# Mouse_Send_SCH.net
KiCad netlist of a schematic drawn in Altium Designer
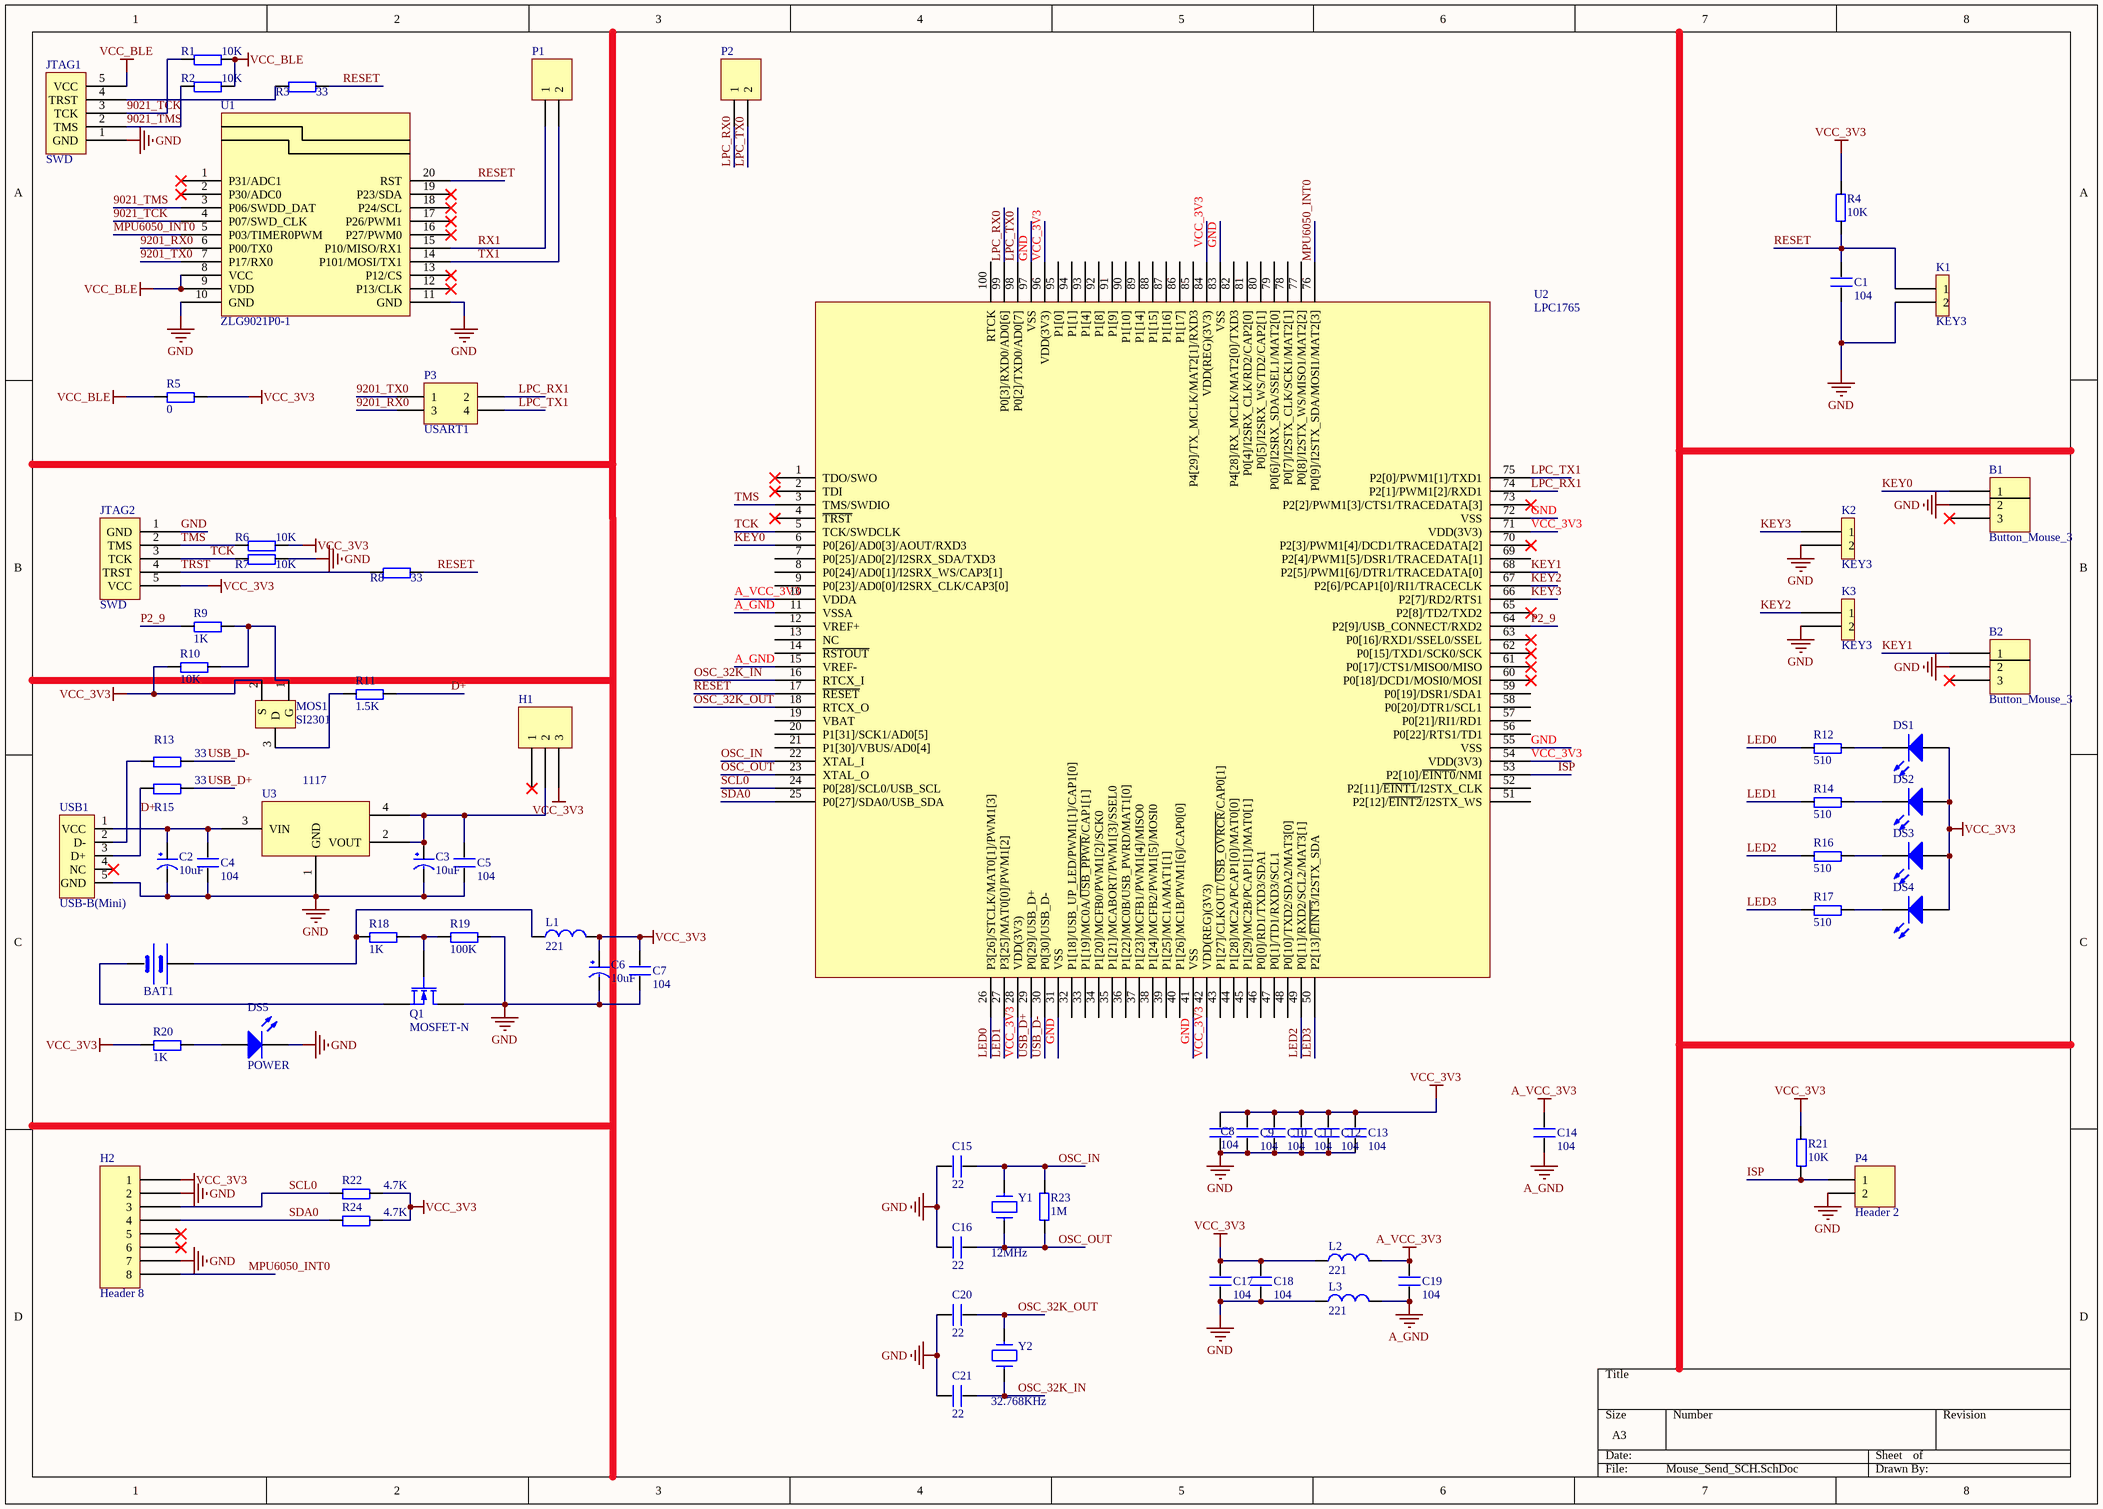
[diagram p0: Mouse_Send_SCH.SchDoc]

(export (version "E")
  (design (tool "Eeschema 10.0.6"))
  (components
    (comp (ref "B1")
      (value "Button_Mouse_3")
      (footprint "Button_Mouse_3")
      (libsource (lib "MY_SCH_Lib") (part "Button_Mouse_3"))
    )
    (comp (ref "B2")
      (value "Button_Mouse_3")
      (footprint "Button_Mouse_3")
      (libsource (lib "MY_SCH_Lib") (part "Button_Mouse_3"))
    )
    (comp (ref "BAT1") (value "BATT") (footprint "BAT_NUM5_2") (libsource (lib "MY_SCH_Lib") (part "BAT")))
    (comp (ref "C1") (value "104") (footprint "0603P") (libsource (lib "MY_SCH_Lib") (part "C")))
    (comp (ref "C2") (value "10uF") (footprint "TAJ_A") (libsource (lib "MY_SCH_Lib") (part "CAP")))
    (comp (ref "C3") (value "10uF") (footprint "TAJ_A") (libsource (lib "MY_SCH_Lib") (part "CAP")))
    (comp (ref "C4") (value "104") (footprint "0603P") (libsource (lib "MY_SCH_Lib") (part "C")))
    (comp (ref "C5") (value "104") (footprint "0603P") (libsource (lib "MY_SCH_Lib") (part "C")))
    (comp (ref "C6") (value "10uF") (footprint "TAJ_A") (libsource (lib "MY_SCH_Lib") (part "CAP")))
    (comp (ref "C7") (value "104") (footprint "0603P") (libsource (lib "MY_SCH_Lib") (part "C")))
    (comp (ref "C8") (value "104") (footprint "0603P") (libsource (lib "MY_SCH_Lib") (part "C")))
    (comp (ref "C9") (value "104") (footprint "0603P") (libsource (lib "MY_SCH_Lib") (part "C")))
    (comp (ref "C10") (value "104") (footprint "0603P") (libsource (lib "MY_SCH_Lib") (part "C")))
    (comp (ref "C11") (value "104") (footprint "0603P") (libsource (lib "MY_SCH_Lib") (part "C")))
    (comp (ref "C12") (value "104") (footprint "0603P") (libsource (lib "MY_SCH_Lib") (part "C")))
    (comp (ref "C13") (value "104") (footprint "0603P") (libsource (lib "MY_SCH_Lib") (part "C")))
    (comp (ref "C14") (value "104") (footprint "0603P") (libsource (lib "MY_SCH_Lib") (part "C")))
    (comp (ref "C15") (value "22") (footprint "0603P") (libsource (lib "MY_SCH_Lib") (part "C")))
    (comp (ref "C16") (value "22") (footprint "0603P") (libsource (lib "MY_SCH_Lib") (part "C")))
    (comp (ref "C17") (value "104") (footprint "0603P") (libsource (lib "MY_SCH_Lib") (part "C")))
    (comp (ref "C18") (value "104") (footprint "0603P") (libsource (lib "MY_SCH_Lib") (part "C")))
    (comp (ref "C19") (value "104") (footprint "0603P") (libsource (lib "MY_SCH_Lib") (part "C")))
    (comp (ref "C20") (value "22") (footprint "0603P") (libsource (lib "MY_SCH_Lib") (part "C")))
    (comp (ref "C21") (value "22") (footprint "0603P") (libsource (lib "MY_SCH_Lib") (part "C")))
    (comp (ref "DS1")
      (value "~")
      (footprint "SMDLED")
      (description "Typical RED, GREEN, YELLOW, AMBER GaAs LED")
      (fields (field (name "PUBLISHER") "Altium Limited"))
      (libsource (lib "MY_SCH_Lib") (part "LED2"))
    )
    (comp (ref "DS2")
      (value "~")
      (footprint "SMDLED")
      (description "Typical RED, GREEN, YELLOW, AMBER GaAs LED")
      (fields (field (name "PUBLISHER") "Altium Limited"))
      (libsource (lib "MY_SCH_Lib") (part "LED2"))
    )
    (comp (ref "DS3")
      (value "~")
      (footprint "SMDLED")
      (description "Typical RED, GREEN, YELLOW, AMBER GaAs LED")
      (fields (field (name "PUBLISHER") "Altium Limited"))
      (libsource (lib "MY_SCH_Lib") (part "LED2"))
    )
    (comp (ref "DS4")
      (value "~")
      (footprint "SMDLED")
      (description "Typical RED, GREEN, YELLOW, AMBER GaAs LED")
      (fields (field (name "PUBLISHER") "Altium Limited"))
      (libsource (lib "MY_SCH_Lib") (part "LED2"))
    )
    (comp (ref "DS5")
      (value "POWER")
      (footprint "SMDLED")
      (description "Typical RED, GREEN, YELLOW, AMBER GaAs LED")
      (fields (field (name "PUBLISHER") "Altium Limited"))
      (libsource (lib "MY_SCH_Lib") (part "LED2"))
    )
    (comp (ref "H1") (value "~") (footprint "KEY_B") (libsource (lib "MY_SCH_Lib") (part "Header 3")))
    (comp (ref "H2")
      (value "Header 8")
      (footprint "Header 8")
      (libsource (lib "MY_SCH_Lib") (part "Header 8"))
    )
    (comp (ref "JTAG1") (value "SWD") (footprint "HEAD5") (libsource (lib "") (part "SWD_1")))
    (comp (ref "JTAG2") (value "SWD") (footprint "HEAD5") (libsource (lib "MY_SCH_Lib") (part "SWD")))
    (comp (ref "K1") (value "KEY3") (footprint "KEY2") (libsource (lib "MY_SCH_Lib") (part "KEY3")))
    (comp (ref "K2") (value "KEY3") (footprint "KEY2") (libsource (lib "MY_SCH_Lib") (part "KEY3")))
    (comp (ref "K3") (value "KEY3") (footprint "KEY2") (libsource (lib "MY_SCH_Lib") (part "KEY3")))
    (comp (ref "L1") (value "221") (footprint "0603P") (libsource (lib "MY_SCH_Lib") (part "Inductor")))
    (comp (ref "L2") (value "221") (footprint "0603P") (libsource (lib "MY_SCH_Lib") (part "Inductor")))
    (comp (ref "L3") (value "221") (footprint "0603P") (libsource (lib "MY_SCH_Lib") (part "Inductor")))
    (comp (ref "MOS1")
      (value "SI2301")
      (footprint "SOT-23")
      (description "IRLML6401/SI2301")
      (libsource (lib "MY_SCH_Lib") (part "MOS-P"))
    )
    (comp (ref "P1")
      (value "~")
      (footprint "HDR1X2")
      (fields (field (name "PUBLISHER") "Altium Limited"))
      (libsource (lib "MY_SCH_Lib") (part "Header 2"))
    )
    (comp (ref "P2")
      (value "~")
      (footprint "HDR1X2")
      (fields (field (name "PUBLISHER") "Altium Limited"))
      (libsource (lib "MY_SCH_Lib") (part "Header 2"))
    )
    (comp (ref "P3")
      (value "USART1")
      (footprint "HDR2X2")
      (description "Header, 2-Pin, Dual row")
      (fields (field (name "PUBLISHER") "Altium Limited"))
      (libsource (lib "MY_SCH_Lib") (part "Header 2X2"))
    )
    (comp (ref "P4")
      (value "Header 2")
      (footprint "HDR1X2")
      (fields (field (name "PUBLISHER") "Altium Limited"))
      (libsource (lib "") (part "Header 2_1"))
    )
    (comp (ref "Q1")
      (value "MOSFET-N")
      (footprint "SOT-23")
      (description "N-Channel MOSFET")
      (fields (field (name "PUBLISHER") "Altium Limited"))
      (libsource (lib "Miscellaneous Devices") (part "MOSFET-N"))
    )
    (comp (ref "R1") (value "10K") (footprint "0603P") (libsource (lib "MY_SCH_Lib") (part "R")))
    (comp (ref "R2") (value "10K") (footprint "0603P") (libsource (lib "MY_SCH_Lib") (part "R")))
    (comp (ref "R3") (value "33") (footprint "0603P") (libsource (lib "MY_SCH_Lib") (part "R")))
    (comp (ref "R4") (value "10K") (footprint "0603P") (libsource (lib "MY_SCH_Lib") (part "R")))
    (comp (ref "R5") (value "0") (footprint "0603P") (libsource (lib "MY_SCH_Lib") (part "R")))
    (comp (ref "R6") (value "10K") (footprint "0603P") (libsource (lib "MY_SCH_Lib") (part "R")))
    (comp (ref "R7") (value "10K") (footprint "0603P") (libsource (lib "MY_SCH_Lib") (part "R")))
    (comp (ref "R8") (value "33") (footprint "0603P") (libsource (lib "MY_SCH_Lib") (part "R")))
    (comp (ref "R9") (value "1K") (footprint "0603P") (libsource (lib "MY_SCH_Lib") (part "R")))
    (comp (ref "R10") (value "10K") (footprint "0603P") (libsource (lib "MY_SCH_Lib") (part "R")))
    (comp (ref "R11") (value "1.5K") (footprint "0603P") (libsource (lib "MY_SCH_Lib") (part "R")))
    (comp (ref "R12") (value "510") (footprint "0603P") (libsource (lib "MY_SCH_Lib") (part "R")))
    (comp (ref "R13") (value "33") (footprint "0603P") (libsource (lib "MY_SCH_Lib") (part "R")))
    (comp (ref "R14") (value "510") (footprint "0603P") (libsource (lib "MY_SCH_Lib") (part "R")))
    (comp (ref "R15") (value "33") (footprint "0603P") (libsource (lib "MY_SCH_Lib") (part "R")))
    (comp (ref "R16") (value "510") (footprint "0603P") (libsource (lib "MY_SCH_Lib") (part "R")))
    (comp (ref "R17") (value "510") (footprint "0603P") (libsource (lib "MY_SCH_Lib") (part "R")))
    (comp (ref "R18") (value "1K") (footprint "0603P") (libsource (lib "MY_SCH_Lib") (part "R")))
    (comp (ref "R19") (value "100K") (footprint "0603P") (libsource (lib "MY_SCH_Lib") (part "R")))
    (comp (ref "R20") (value "1K") (footprint "0603P") (libsource (lib "MY_SCH_Lib") (part "R")))
    (comp (ref "R21") (value "10K") (footprint "0603P") (libsource (lib "MY_SCH_Lib") (part "R")))
    (comp (ref "R22") (value "4.7K") (footprint "0603P") (libsource (lib "MY_SCH_Lib") (part "R")))
    (comp (ref "R23") (value "1M") (footprint "0603P") (libsource (lib "MY_SCH_Lib") (part "R")))
    (comp (ref "R24") (value "4.7K") (footprint "0603P") (libsource (lib "MY_SCH_Lib") (part "R")))
    (comp (ref "U1")
      (value "ZLG9021P0-1")
      (footprint "ZLG9021P0-1")
      (libsource (lib "MY_SCH_Lib") (part "ZLG9021P0-1"))
    )
    (comp (ref "U2")
      (value "LPC1765")
      (footprint "TQFP-100")
      (libsource (lib "LPC17xx_System_Sch_AD") (part "LPC1765"))
    )
    (comp (ref "U3") (value "1117") (footprint "AMS1117") (libsource (lib "MY_SCH_Lib") (part "1117")))
    (comp (ref "USB1")
      (value "USB-B(Mini)")
      (footprint "USB/SM0.8-6H5")
      (libsource (lib "MY_SCH_Lib") (part "USB5"))
    )
    (comp (ref "Y1")
      (value "12MHz")
      (footprint "XTAL_US")
      (description "Crystal")
      (libsource (lib "LPC17xx_System_Sch_AD") (part "CRYSTAL"))
    )
    (comp (ref "Y2")
      (value "32.768KHz")
      (footprint "CRY-32")
      (description "Crystal")
      (libsource (lib "LPC17xx_System_Sch_AD") (part "CRYSTAL"))
    )
  )
  (nets
    (net (code "1") (name "/9021_TCK") (class "Default")
      (node (ref "JTAG1") (pin "3") (pinfunction "TCK_3") (pintype "passive"))
      (node (ref "R1") (pin "1") (pintype "passive"))
      (node (ref "U1") (pin "4") (pinfunction "P07/SWD_CLK_4") (pintype "passive"))
    )
    (net (code "2") (name "/9021_TMS") (class "Default")
      (node (ref "JTAG1") (pin "2") (pinfunction "TMS_2") (pintype "passive"))
      (node (ref "R2") (pin "1") (pintype "passive"))
      (node (ref "U1") (pin "3") (pinfunction "P06/SWDD_DAT_3") (pintype "passive"))
    )
    (net (code "3") (name "/9201_RX0") (class "Default")
      (node (ref "P3") (pin "3") (pinfunction "3_3") (pintype "passive"))
      (node (ref "U1") (pin "6") (pinfunction "P00/TX0_6") (pintype "passive"))
    )
    (net (code "4") (name "/9201_TX0") (class "Default")
      (node (ref "P3") (pin "1") (pinfunction "1_1") (pintype "passive"))
      (node (ref "U1") (pin "7") (pinfunction "P17/RX0_7") (pintype "passive"))
    )
    (net (code "5") (name "/D+") (class "Default")
      (node (ref "R11") (pin "2") (pintype "passive"))
      (node (ref "R15") (pin "1") (pintype "passive"))
      (node (ref "USB1") (pin "3") (pinfunction "D+_3") (pintype "passive"))
    )
    (net (code "6") (name "/ISP") (class "Default")
      (node (ref "P4") (pin "1") (pinfunction "1_1") (pintype "passive"))
      (node (ref "R21") (pin "1") (pintype "passive"))
      (node (ref "U2") (pin "53") (pinfunction "P2[10]/~{EINT0}/NMI_53") (pintype "passive"))
    )
    (net (code "7") (name "/KEY0") (class "Default")
      (node (ref "B1") (pin "1") (pinfunction "1_1") (pintype "passive"))
      (node (ref "U2") (pin "6") (pinfunction "P0[26]/AD0[3]/AOUT/RXD3_6") (pintype "passive"))
    )
    (net (code "8") (name "/KEY1") (class "Default")
      (node (ref "B2") (pin "1") (pinfunction "1_1") (pintype "passive"))
      (node (ref "U2") (pin "68") (pinfunction "P2[5]/PWM1[6]/DTR1/TRACEDATA[0]_68") (pintype "passive"))
    )
    (net (code "9") (name "/KEY2") (class "Default")
      (node (ref "K3") (pin "1") (pinfunction "1_1") (pintype "passive"))
      (node (ref "U2") (pin "67") (pinfunction "P2[6]/PCAP1[0]/RI1/TRACECLK_67") (pintype "passive"))
    )
    (net (code "10") (name "/KEY3") (class "Default")
      (node (ref "K2") (pin "1") (pinfunction "1_1") (pintype "passive"))
      (node (ref "U2") (pin "66") (pinfunction "P2[7]/RD2/RTS1_66") (pintype "passive"))
    )
    (net (code "11") (name "/LED0") (class "Default")
      (node (ref "R12") (pin "1") (pintype "passive"))
      (node (ref "U2") (pin "26") (pinfunction "P3[26]/STCLK/MAT0[1]/PWM1[3]_26") (pintype "passive"))
    )
    (net (code "12") (name "/LED1") (class "Default")
      (node (ref "R14") (pin "1") (pintype "passive"))
      (node (ref "U2") (pin "27") (pinfunction "P3[25]/MAT0[0]/PWM1[2]_27") (pintype "passive"))
    )
    (net (code "13") (name "/LED2") (class "Default")
      (node (ref "R16") (pin "1") (pintype "passive"))
      (node (ref "U2") (pin "49") (pinfunction "P0[11]/RXD2/SCL2/MAT3[1]_49") (pintype "passive"))
    )
    (net (code "14") (name "/LED3") (class "Default")
      (node (ref "R17") (pin "1") (pintype "passive"))
      (node (ref "U2") (pin "50") (pinfunction "P2[13]/~{EINT3}/I2STX_SDA_50") (pintype "passive"))
    )
    (net (code "15") (name "/LPC_RX0") (class "Default")
      (node (ref "P2") (pin "1") (pinfunction "1_1") (pintype "passive"))
      (node (ref "U2") (pin "99") (pinfunction "P0[3]/RXD0/AD0[6]_99") (pintype "passive"))
    )
    (net (code "16") (name "/LPC_RX1") (class "Default")
      (node (ref "P3") (pin "2") (pinfunction "2_2") (pintype "passive"))
      (node (ref "U2") (pin "74") (pinfunction "P2[1]/PWM1[2]/RXD1_74") (pintype "passive"))
    )
    (net (code "17") (name "/LPC_TX0") (class "Default")
      (node (ref "P2") (pin "2") (pinfunction "2_2") (pintype "passive"))
      (node (ref "U2") (pin "98") (pinfunction "P0[2]/TXD0/AD0[7]_98") (pintype "passive"))
    )
    (net (code "18") (name "/LPC_TX1") (class "Default")
      (node (ref "P3") (pin "4") (pinfunction "4_4") (pintype "passive"))
      (node (ref "U2") (pin "75") (pinfunction "P2[0]/PWM1[1]/TXD1_75") (pintype "passive"))
    )
    (net (code "19") (name "/MPU6050_INT0") (class "Default")
      (node (ref "H2") (pin "8") (pinfunction "8_8") (pintype "passive"))
      (node (ref "U1") (pin "5") (pinfunction "P03/TIMER0PWM_5") (pintype "passive"))
      (node (ref "U2") (pin "76") (pinfunction "P0[9]/I2STX_SDA/MOSI1/MAT2[3]_76") (pintype "passive"))
    )
    (net (code "20") (name "/OSC_32K_IN") (class "Default")
      (node (ref "C21") (pin "2") (pintype "passive"))
      (node (ref "U2") (pin "16") (pinfunction "RTCX_I_16") (pintype "passive"))
      (node (ref "Y2") (pin "1") (pinfunction "1_1") (pintype "passive"))
    )
    (net (code "21") (name "/OSC_32K_OUT") (class "Default")
      (node (ref "C20") (pin "2") (pintype "passive"))
      (node (ref "U2") (pin "18") (pinfunction "RTCX_O_18") (pintype "passive"))
      (node (ref "Y2") (pin "2") (pinfunction "2_2") (pintype "passive"))
    )
    (net (code "22") (name "/OSC_IN") (class "Default")
      (node (ref "C15") (pin "2") (pintype "passive"))
      (node (ref "R23") (pin "1") (pintype "passive"))
      (node (ref "U2") (pin "22") (pinfunction "XTAL_I_22") (pintype "passive"))
      (node (ref "Y1") (pin "2") (pinfunction "2_2") (pintype "passive"))
    )
    (net (code "23") (name "/OSC_OUT") (class "Default")
      (node (ref "C16") (pin "2") (pintype "passive"))
      (node (ref "R23") (pin "2") (pintype "passive"))
      (node (ref "U2") (pin "23") (pinfunction "XTAL_O_23") (pintype "passive"))
      (node (ref "Y1") (pin "1") (pinfunction "1_1") (pintype "passive"))
    )
    (net (code "24") (name "/P2_9") (class "Default")
      (node (ref "R9") (pin "1") (pintype "passive"))
      (node (ref "U2") (pin "64") (pinfunction "P2[9]/USB_CONNECT/RXD2_64") (pintype "passive"))
    )
    (net (code "25") (name "/RESET") (class "Default")
      (node (ref "C1") (pin "2") (pintype "passive"))
      (node (ref "K1") (pin "1") (pinfunction "1_1") (pintype "passive"))
      (node (ref "R3") (pin "2") (pintype "passive"))
      (node (ref "R4") (pin "1") (pintype "passive"))
      (node (ref "R8") (pin "2") (pintype "passive"))
      (node (ref "U1") (pin "20") (pinfunction "RST_20") (pintype "passive"))
      (node (ref "U2") (pin "17") (pinfunction "~{RESET}_17") (pintype "passive"))
    )
    (net (code "26") (name "/RX1") (class "Default")
      (node (ref "P1") (pin "1") (pinfunction "1_1") (pintype "passive"))
      (node (ref "U1") (pin "15") (pinfunction "P10/MISO/RX1_15") (pintype "passive"))
    )
    (net (code "27") (name "/SCL0") (class "Default")
      (node (ref "H2") (pin "3") (pinfunction "3_3") (pintype "passive"))
      (node (ref "R22") (pin "1") (pintype "passive"))
      (node (ref "U2") (pin "24") (pinfunction "P0[28]/SCL0/USB_SCL_24") (pintype "passive"))
    )
    (net (code "28") (name "/SDA0") (class "Default")
      (node (ref "H2") (pin "4") (pinfunction "4_4") (pintype "passive"))
      (node (ref "R24") (pin "1") (pintype "passive"))
      (node (ref "U2") (pin "25") (pinfunction "P0[27]/SDA0/USB_SDA_25") (pintype "passive"))
    )
    (net (code "29") (name "/TCK") (class "Default")
      (node (ref "JTAG2") (pin "3") (pinfunction "TCK_3") (pintype "passive"))
      (node (ref "R7") (pin "1") (pintype "passive"))
      (node (ref "U2") (pin "5") (pinfunction "TCK/SWDCLK_5") (pintype "passive"))
    )
    (net (code "30") (name "/TMS") (class "Default")
      (node (ref "JTAG2") (pin "2") (pinfunction "TMS_2") (pintype "passive"))
      (node (ref "R6") (pin "1") (pintype "passive"))
      (node (ref "U2") (pin "3") (pinfunction "TMS/SWDIO_3") (pintype "passive"))
    )
    (net (code "31") (name "/TRST") (class "Default")
      (node (ref "JTAG2") (pin "4") (pinfunction "TRST_4") (pintype "passive"))
      (node (ref "R8") (pin "1") (pintype "passive"))
    )
    (net (code "32") (name "/TX1") (class "Default")
      (node (ref "P1") (pin "2") (pinfunction "2_2") (pintype "passive"))
      (node (ref "U1") (pin "14") (pinfunction "P101/MOSI/TX1_14") (pintype "passive"))
    )
    (net (code "33") (name "/USB_D+") (class "Default")
      (node (ref "R15") (pin "2") (pintype "passive"))
      (node (ref "U2") (pin "29") (pinfunction "P0[29]/USB_D+_29") (pintype "passive"))
    )
    (net (code "34") (name "/USB_D-") (class "Default")
      (node (ref "R13") (pin "2") (pintype "passive"))
      (node (ref "U2") (pin "30") (pinfunction "P0[30]/USB_D-_30") (pintype "passive"))
    )
    (net (code "35") (name "A_GND") (class "Default")
      (node (ref "C14") (pin "2") (pintype "passive"))
      (node (ref "C19") (pin "1") (pintype "passive"))
      (node (ref "L3") (pin "2") (pinfunction "2_2") (pintype "passive"))
      (node (ref "U2") (pin "11") (pinfunction "VSSA_11") (pintype "passive"))
      (node (ref "U2") (pin "15") (pinfunction "VREF-_15") (pintype "passive"))
    )
    (net (code "36") (name "A_VCC_3V3") (class "Default")
      (node (ref "C14") (pin "1") (pintype "passive"))
      (node (ref "C19") (pin "2") (pintype "passive"))
      (node (ref "L2") (pin "2") (pinfunction "2_2") (pintype "passive"))
      (node (ref "U2") (pin "10") (pinfunction "VDDA_10") (pintype "passive"))
    )
    (net (code "37") (name "GND") (class "Default")
      (node (ref "B1") (pin "2") (pinfunction "2_2") (pintype "passive"))
      (node (ref "B2") (pin "2") (pinfunction "2_2") (pintype "passive"))
      (node (ref "C1") (pin "1") (pintype "passive"))
      (node (ref "C10") (pin "2") (pintype "passive"))
      (node (ref "C11") (pin "2") (pintype "passive"))
      (node (ref "C12") (pin "2") (pintype "passive"))
      (node (ref "C13") (pin "2") (pintype "passive"))
      (node (ref "C15") (pin "1") (pintype "passive"))
      (node (ref "C16") (pin "1") (pintype "passive"))
      (node (ref "C17") (pin "1") (pintype "passive"))
      (node (ref "C18") (pin "1") (pintype "passive"))
      (node (ref "C2") (pin "2") (pinfunction "GND_2") (pintype "passive"))
      (node (ref "C20") (pin "1") (pintype "passive"))
      (node (ref "C21") (pin "1") (pintype "passive"))
      (node (ref "C3") (pin "2") (pinfunction "GND_2") (pintype "passive"))
      (node (ref "C4") (pin "1") (pintype "passive"))
      (node (ref "C5") (pin "1") (pintype "passive"))
      (node (ref "C6") (pin "2") (pinfunction "GND_2") (pintype "passive"))
      (node (ref "C7") (pin "1") (pintype "passive"))
      (node (ref "C8") (pin "2") (pintype "passive"))
      (node (ref "C9") (pin "2") (pintype "passive"))
      (node (ref "DS5") (pin "2") (pinfunction "K_2") (pintype "passive"))
      (node (ref "H2") (pin "2") (pinfunction "2_2") (pintype "passive"))
      (node (ref "H2") (pin "7") (pinfunction "7_7") (pintype "passive"))
      (node (ref "JTAG1") (pin "1") (pinfunction "GND_1") (pintype "passive"))
      (node (ref "JTAG2") (pin "1") (pinfunction "GND_1") (pintype "passive"))
      (node (ref "K1") (pin "2") (pinfunction "2_2") (pintype "passive"))
      (node (ref "K2") (pin "2") (pinfunction "2_2") (pintype "passive"))
      (node (ref "K3") (pin "2") (pinfunction "2_2") (pintype "passive"))
      (node (ref "L3") (pin "1") (pinfunction "1_1") (pintype "passive"))
      (node (ref "P4") (pin "2") (pinfunction "2_2") (pintype "passive"))
      (node (ref "Q1") (pin "1") (pinfunction "D_1") (pintype "passive"))
      (node (ref "R19") (pin "2") (pintype "passive"))
      (node (ref "R7") (pin "2") (pintype "passive"))
      (node (ref "U1") (pin "10") (pinfunction "GND_10") (pintype "passive"))
      (node (ref "U1") (pin "11") (pinfunction "GND_11") (pintype "passive"))
      (node (ref "U2") (pin "31") (pinfunction "VSS_31") (pintype "passive"))
      (node (ref "U2") (pin "41") (pinfunction "VSS_41") (pintype "passive"))
      (node (ref "U2") (pin "55") (pinfunction "VSS_55") (pintype "passive"))
      (node (ref "U2") (pin "72") (pinfunction "VSS_72") (pintype "passive"))
      (node (ref "U2") (pin "83") (pinfunction "VSS_83") (pintype "passive"))
      (node (ref "U2") (pin "97") (pinfunction "VSS_97") (pintype "passive"))
      (node (ref "U3") (pin "1") (pinfunction "GND_1") (pintype "passive"))
      (node (ref "USB1") (pin "5") (pinfunction "GND_5") (pintype "passive"))
    )
    (net (code "38") (name "Net-(BAT1-GND)") (class "Default")
      (node (ref "BAT1") (pin "2") (pinfunction "GND_2") (pintype "passive"))
      (node (ref "Q1") (pin "3") (pinfunction "S_3") (pintype "passive"))
    )
    (net (code "39") (name "Net-(BAT1-VCC)") (class "Default")
      (node (ref "BAT1") (pin "1") (pinfunction "VCC_1") (pintype "passive"))
      (node (ref "L1") (pin "1") (pinfunction "1_1") (pintype "passive"))
      (node (ref "R18") (pin "1") (pintype "passive"))
    )
    (net (code "40") (name "Net-(C2-VCC)") (class "Default")
      (node (ref "C2") (pin "1") (pinfunction "VCC_1") (pintype "passive"))
      (node (ref "C4") (pin "2") (pintype "passive"))
      (node (ref "U3") (pin "3") (pinfunction "VIN_3") (pintype "passive"))
      (node (ref "USB1") (pin "1") (pinfunction "VCC_1") (pintype "passive"))
    )
    (net (code "41") (name "Net-(C3-VCC)") (class "Default")
      (node (ref "C3") (pin "1") (pinfunction "VCC_1") (pintype "passive"))
      (node (ref "C5") (pin "2") (pintype "passive"))
      (node (ref "H1") (pin "2") (pinfunction "2_2") (pintype "passive"))
      (node (ref "U3") (pin "2") (pinfunction "VOUT_2") (pintype "passive"))
      (node (ref "U3") (pin "4") (pinfunction "4_4") (pintype "passive"))
    )
    (net (code "42") (name "Net-(DS1-K)") (class "Default")
      (node (ref "DS1") (pin "2") (pinfunction "K_2") (pintype "passive"))
      (node (ref "R12") (pin "2") (pintype "passive"))
    )
    (net (code "43") (name "Net-(DS2-K)") (class "Default")
      (node (ref "DS2") (pin "2") (pinfunction "K_2") (pintype "passive"))
      (node (ref "R14") (pin "2") (pintype "passive"))
    )
    (net (code "44") (name "Net-(DS3-K)") (class "Default")
      (node (ref "DS3") (pin "2") (pinfunction "K_2") (pintype "passive"))
      (node (ref "R16") (pin "2") (pintype "passive"))
    )
    (net (code "45") (name "Net-(DS4-K)") (class "Default")
      (node (ref "DS4") (pin "2") (pinfunction "K_2") (pintype "passive"))
      (node (ref "R17") (pin "2") (pintype "passive"))
    )
    (net (code "46") (name "Net-(DS5-A)") (class "Default")
      (node (ref "DS5") (pin "1") (pinfunction "A_1") (pintype "passive"))
      (node (ref "R20") (pin "2") (pintype "passive"))
    )
    (net (code "47") (name "Net-(JTAG1-TRST)") (class "Default")
      (node (ref "JTAG1") (pin "4") (pinfunction "TRST_4") (pintype "passive"))
      (node (ref "R3") (pin "1") (pintype "passive"))
    )
    (net (code "48") (name "Net-(MOS1-D)") (class "Default")
      (node (ref "MOS1") (pin "3") (pinfunction "D_3") (pintype "passive"))
      (node (ref "R11") (pin "1") (pintype "passive"))
    )
    (net (code "49") (name "Net-(MOS1-G)") (class "Default")
      (node (ref "MOS1") (pin "1") (pinfunction "G_1") (pintype "passive"))
      (node (ref "R10") (pin "2") (pintype "passive"))
      (node (ref "R9") (pin "2") (pintype "passive"))
    )
    (net (code "50") (name "Net-(Q1-G)") (class "Default")
      (node (ref "Q1") (pin "2") (pinfunction "G_2") (pintype "passive"))
      (node (ref "R18") (pin "2") (pintype "passive"))
      (node (ref "R19") (pin "1") (pintype "passive"))
    )
    (net (code "51") (name "Net-(USB1-D-)") (class "Default")
      (node (ref "R13") (pin "1") (pintype "passive"))
      (node (ref "USB1") (pin "2") (pinfunction "D-_2") (pintype "passive"))
    )
    (net (code "52") (name "VCC_3V3") (class "Default")
      (node (ref "C10") (pin "1") (pintype "passive"))
      (node (ref "C11") (pin "1") (pintype "passive"))
      (node (ref "C12") (pin "1") (pintype "passive"))
      (node (ref "C13") (pin "1") (pintype "passive"))
      (node (ref "C17") (pin "2") (pintype "passive"))
      (node (ref "C18") (pin "2") (pintype "passive"))
      (node (ref "C6") (pin "1") (pinfunction "VCC_1") (pintype "passive"))
      (node (ref "C7") (pin "2") (pintype "passive"))
      (node (ref "C8") (pin "1") (pintype "passive"))
      (node (ref "C9") (pin "1") (pintype "passive"))
      (node (ref "DS1") (pin "1") (pinfunction "A_1") (pintype "passive"))
      (node (ref "DS2") (pin "1") (pinfunction "A_1") (pintype "passive"))
      (node (ref "DS3") (pin "1") (pinfunction "A_1") (pintype "passive"))
      (node (ref "DS4") (pin "1") (pinfunction "A_1") (pintype "passive"))
      (node (ref "H1") (pin "3") (pinfunction "3_3") (pintype "passive"))
      (node (ref "H2") (pin "1") (pinfunction "1_1") (pintype "passive"))
      (node (ref "JTAG2") (pin "5") (pinfunction "VCC_5") (pintype "passive"))
      (node (ref "L1") (pin "2") (pinfunction "2_2") (pintype "passive"))
      (node (ref "L2") (pin "1") (pinfunction "1_1") (pintype "passive"))
      (node (ref "MOS1") (pin "2") (pinfunction "S_2") (pintype "passive"))
      (node (ref "R10") (pin "1") (pintype "passive"))
      (node (ref "R20") (pin "1") (pintype "passive"))
      (node (ref "R21") (pin "2") (pintype "passive"))
      (node (ref "R22") (pin "2") (pintype "passive"))
      (node (ref "R24") (pin "2") (pintype "passive"))
      (node (ref "R4") (pin "2") (pintype "passive"))
      (node (ref "R5") (pin "2") (pintype "passive"))
      (node (ref "R6") (pin "2") (pintype "passive"))
      (node (ref "U2") (pin "28") (pinfunction "VDD(3V3)_28") (pintype "passive"))
      (node (ref "U2") (pin "42") (pinfunction "VDD(REG)(3V3)_42") (pintype "passive"))
      (node (ref "U2") (pin "54") (pinfunction "VDD(3V3)_54") (pintype "passive"))
      (node (ref "U2") (pin "71") (pinfunction "VDD(3V3)_71") (pintype "passive"))
      (node (ref "U2") (pin "84") (pinfunction "VDD(REG)(3V3)_84") (pintype "passive"))
      (node (ref "U2") (pin "96") (pinfunction "VDD(3V3)_96") (pintype "passive"))
    )
    (net (code "53") (name "VCC_BLE") (class "Default")
      (node (ref "JTAG1") (pin "5") (pinfunction "VCC_5") (pintype "passive"))
      (node (ref "R1") (pin "2") (pintype "passive"))
      (node (ref "R2") (pin "2") (pintype "passive"))
      (node (ref "R5") (pin "1") (pintype "passive"))
      (node (ref "U1") (pin "8") (pinfunction "VCC_8") (pintype "passive"))
      (node (ref "U1") (pin "9") (pinfunction "VDD_9") (pintype "passive"))
    )
    (net (code "54") (name "unconnected-(B1-Pad3)") (class "Default")
      (node (ref "B1") (pin "3") (pinfunction "3_3") (pintype "passive+no_connect"))
    )
    (net (code "55") (name "unconnected-(B2-Pad3)") (class "Default")
      (node (ref "B2") (pin "3") (pinfunction "3_3") (pintype "passive+no_connect"))
    )
    (net (code "56") (name "unconnected-(H1-Pad1)") (class "Default")
      (node (ref "H1") (pin "1") (pinfunction "1_1") (pintype "passive+no_connect"))
    )
    (net (code "57") (name "unconnected-(H2-Pad5)") (class "Default")
      (node (ref "H2") (pin "5") (pinfunction "5_5") (pintype "passive+no_connect"))
    )
    (net (code "58") (name "unconnected-(H2-Pad6)") (class "Default")
      (node (ref "H2") (pin "6") (pinfunction "6_6") (pintype "passive+no_connect"))
    )
    (net (code "59") (name "unconnected-(U1-P12{slash}CS-Pad13)") (class "Default")
      (node (ref "U1") (pin "13") (pinfunction "P12/CS_13") (pintype "passive+no_connect"))
    )
    (net (code "60") (name "unconnected-(U1-P13{slash}CLK-Pad12)") (class "Default")
      (node (ref "U1") (pin "12") (pinfunction "P13/CLK_12") (pintype "passive+no_connect"))
    )
    (net (code "61") (name "unconnected-(U1-P23{slash}SDA-Pad19)") (class "Default")
      (node (ref "U1") (pin "19") (pinfunction "P23/SDA_19") (pintype "passive+no_connect"))
    )
    (net (code "62") (name "unconnected-(U1-P24{slash}SCL-Pad18)") (class "Default")
      (node (ref "U1") (pin "18") (pinfunction "P24/SCL_18") (pintype "passive+no_connect"))
    )
    (net (code "63") (name "unconnected-(U1-P26{slash}PWM1-Pad17)") (class "Default")
      (node (ref "U1") (pin "17") (pinfunction "P26/PWM1_17") (pintype "passive+no_connect"))
    )
    (net (code "64") (name "unconnected-(U1-P27{slash}PWM0-Pad16)") (class "Default")
      (node (ref "U1") (pin "16") (pinfunction "P27/PWM0_16") (pintype "passive+no_connect"))
    )
    (net (code "65") (name "unconnected-(U1-P30{slash}ADC0-Pad2)") (class "Default")
      (node (ref "U1") (pin "2") (pinfunction "P30/ADC0_2") (pintype "passive+no_connect"))
    )
    (net (code "66") (name "unconnected-(U1-P31{slash}ADC1-Pad1)") (class "Default")
      (node (ref "U1") (pin "1") (pinfunction "P31/ADC1_1") (pintype "passive+no_connect"))
    )
    (net (code "67") (name "unconnected-(U2-NC-Pad13)") (class "Default")
      (node (ref "U2") (pin "13") (pinfunction "NC_13") (pintype "passive"))
    )
    (net (code "68") (name "unconnected-(U2-P0[0]{slash}RD1{slash}TXD3{slash}SDA1-Pad46)") (class "Default")
      (node (ref "U2") (pin "46") (pinfunction "P0[0]/RD1/TXD3/SDA1_46") (pintype "passive"))
    )
    (net (code "69") (name "unconnected-(U2-P0[1]{slash}TD1{slash}RXD3{slash}SCL1-Pad47)") (class "Default")
      (node (ref "U2") (pin "47") (pinfunction "P0[1]/TD1/RXD3/SCL1_47") (pintype "passive"))
    )
    (net (code "70") (name "unconnected-(U2-P0[4]{slash}I2SRX_CLK{slash}RD2{slash}CAP2[0]-Pad81)") (class "Default")
      (node (ref "U2") (pin "81") (pinfunction "P0[4]/I2SRX_CLK/RD2/CAP2[0]_81") (pintype "passive"))
    )
    (net (code "71") (name "unconnected-(U2-P0[5]{slash}I2SRX_WS{slash}TD2{slash}CAP2[1]-Pad80)") (class "Default")
      (node (ref "U2") (pin "80") (pinfunction "P0[5]/I2SRX_WS/TD2/CAP2[1]_80") (pintype "passive"))
    )
    (net (code "72") (name "unconnected-(U2-P0[6]{slash}I2SRX_SDA{slash}SSEL1{slash}MAT2[0]-Pad79)") (class "Default")
      (node (ref "U2") (pin "79") (pinfunction "P0[6]/I2SRX_SDA/SSEL1/MAT2[0]_79") (pintype "passive"))
    )
    (net (code "73") (name "unconnected-(U2-P0[7]{slash}I2STX_CLK{slash}SCK1{slash}MAT2[1]-Pad78)") (class "Default")
      (node (ref "U2") (pin "78") (pinfunction "P0[7]/I2STX_CLK/SCK1/MAT2[1]_78") (pintype "passive"))
    )
    (net (code "74") (name "unconnected-(U2-P0[8]{slash}I2STX_WS{slash}MISO1{slash}MAT2[2]-Pad77)") (class "Default")
      (node (ref "U2") (pin "77") (pinfunction "P0[8]/I2STX_WS/MISO1/MAT2[2]_77") (pintype "passive"))
    )
    (net (code "75") (name "unconnected-(U2-P0[10]{slash}TXD2{slash}SDA2{slash}MAT3[0]-Pad48)") (class "Default")
      (node (ref "U2") (pin "48") (pinfunction "P0[10]/TXD2/SDA2/MAT3[0]_48") (pintype "passive"))
    )
    (net (code "76") (name "unconnected-(U2-P0[15]{slash}TXD1{slash}SCK0{slash}SCK-Pad62)") (class "Default")
      (node (ref "U2") (pin "62") (pinfunction "P0[15]/TXD1/SCK0/SCK_62") (pintype "passive+no_connect"))
    )
    (net (code "77") (name "unconnected-(U2-P0[16]{slash}RXD1{slash}SSEL0{slash}SSEL-Pad63)") (class "Default")
      (node (ref "U2") (pin "63") (pinfunction "P0[16]/RXD1/SSEL0/SSEL_63") (pintype "passive+no_connect"))
    )
    (net (code "78") (name "unconnected-(U2-P0[17]{slash}CTS1{slash}MISO0{slash}MISO-Pad61)") (class "Default")
      (node (ref "U2") (pin "61") (pinfunction "P0[17]/CTS1/MISO0/MISO_61") (pintype "passive+no_connect"))
    )
    (net (code "79") (name "unconnected-(U2-P0[18]{slash}DCD1{slash}MOSI0{slash}MOSI-Pad60)") (class "Default")
      (node (ref "U2") (pin "60") (pinfunction "P0[18]/DCD1/MOSI0/MOSI_60") (pintype "passive+no_connect"))
    )
    (net (code "80") (name "unconnected-(U2-P0[19]{slash}DSR1{slash}SDA1-Pad59)") (class "Default")
      (node (ref "U2") (pin "59") (pinfunction "P0[19]/DSR1/SDA1_59") (pintype "passive"))
    )
    (net (code "81") (name "unconnected-(U2-P0[20]{slash}DTR1{slash}SCL1-Pad58)") (class "Default")
      (node (ref "U2") (pin "58") (pinfunction "P0[20]/DTR1/SCL1_58") (pintype "passive"))
    )
    (net (code "82") (name "unconnected-(U2-P0[21]{slash}RI1{slash}RD1-Pad57)") (class "Default")
      (node (ref "U2") (pin "57") (pinfunction "P0[21]/RI1/RD1_57") (pintype "passive"))
    )
    (net (code "83") (name "unconnected-(U2-P0[22]{slash}RTS1{slash}TD1-Pad56)") (class "Default")
      (node (ref "U2") (pin "56") (pinfunction "P0[22]/RTS1/TD1_56") (pintype "passive"))
    )
    (net (code "84") (name "unconnected-(U2-P0[23]{slash}AD0[0]{slash}I2SRX_CLK{slash}CAP3[0]-Pad9)") (class "Default")
      (node (ref "U2") (pin "9") (pinfunction "P0[23]/AD0[0]/I2SRX_CLK/CAP3[0]_9") (pintype "passive"))
    )
    (net (code "85") (name "unconnected-(U2-P0[24]{slash}AD0[1]{slash}I2SRX_WS{slash}CAP3[1]-Pad8)") (class "Default")
      (node (ref "U2") (pin "8") (pinfunction "P0[24]/AD0[1]/I2SRX_WS/CAP3[1]_8") (pintype "passive"))
    )
    (net (code "86") (name "unconnected-(U2-P0[25]{slash}AD0[2]{slash}I2SRX_SDA{slash}TXD3-Pad7)") (class "Default")
      (node (ref "U2") (pin "7") (pinfunction "P0[25]/AD0[2]/I2SRX_SDA/TXD3_7") (pintype "passive"))
    )
    (net (code "87") (name "unconnected-(U2-P1[0]-Pad95)") (class "Default")
      (node (ref "U2") (pin "95") (pinfunction "P1[0]_95") (pintype "passive"))
    )
    (net (code "88") (name "unconnected-(U2-P1[1]-Pad94)") (class "Default")
      (node (ref "U2") (pin "94") (pinfunction "P1[1]_94") (pintype "passive"))
    )
    (net (code "89") (name "unconnected-(U2-P1[4]-Pad93)") (class "Default")
      (node (ref "U2") (pin "93") (pinfunction "P1[4]_93") (pintype "passive"))
    )
    (net (code "90") (name "unconnected-(U2-P1[8]-Pad92)") (class "Default")
      (node (ref "U2") (pin "92") (pinfunction "P1[8]_92") (pintype "passive"))
    )
    (net (code "91") (name "unconnected-(U2-P1[9]-Pad91)") (class "Default")
      (node (ref "U2") (pin "91") (pinfunction "P1[9]_91") (pintype "passive"))
    )
    (net (code "92") (name "unconnected-(U2-P1[10]-Pad90)") (class "Default")
      (node (ref "U2") (pin "90") (pinfunction "P1[10]_90") (pintype "passive"))
    )
    (net (code "93") (name "unconnected-(U2-P1[14]-Pad89)") (class "Default")
      (node (ref "U2") (pin "89") (pinfunction "P1[14]_89") (pintype "passive"))
    )
    (net (code "94") (name "unconnected-(U2-P1[15]-Pad88)") (class "Default")
      (node (ref "U2") (pin "88") (pinfunction "P1[15]_88") (pintype "passive"))
    )
    (net (code "95") (name "unconnected-(U2-P1[16]-Pad87)") (class "Default")
      (node (ref "U2") (pin "87") (pinfunction "P1[16]_87") (pintype "passive"))
    )
    (net (code "96") (name "unconnected-(U2-P1[17]-Pad86)") (class "Default")
      (node (ref "U2") (pin "86") (pinfunction "P1[17]_86") (pintype "passive"))
    )
    (net (code "97") (name "unconnected-(U2-P1[18]{slash}USB_UP_LED{slash}PWM1[1]{slash}CAP1[0]-Pad32)") (class "Default")
      (node (ref "U2") (pin "32") (pinfunction "P1[18]/USB_UP_LED/PWM1[1]/CAP1[0]_32") (pintype "passive"))
    )
    (net (code "98") (name "unconnected-(U2-P1[19]{slash}MC0A{slash}~{USB_PPWR}{slash}CAP1[1]-Pad33)") (class "Default")
      (node (ref "U2") (pin "33") (pinfunction "P1[19]/MC0A/~{USB_PPWR}/CAP1[1]_33") (pintype "passive"))
    )
    (net (code "99") (name "unconnected-(U2-P1[20]{slash}MCFB0{slash}PWM1[2]{slash}SCK0-Pad34)") (class "Default")
      (node (ref "U2") (pin "34") (pinfunction "P1[20]/MCFB0/PWM1[2]/SCK0_34") (pintype "passive"))
    )
    (net (code "100") (name "unconnected-(U2-P1[21]{slash}MCABORT{slash}PWM1[3]{slash}SSEL0-Pad35)") (class "Default")
      (node (ref "U2") (pin "35") (pinfunction "P1[21]/MCABORT/PWM1[3]/SSEL0_35") (pintype "passive"))
    )
    (net (code "101") (name "unconnected-(U2-P1[22]{slash}MC0B{slash}USB_PWRD{slash}MAT1[0]-Pad36)") (class "Default")
      (node (ref "U2") (pin "36") (pinfunction "P1[22]/MC0B/USB_PWRD/MAT1[0]_36") (pintype "passive"))
    )
    (net (code "102") (name "unconnected-(U2-P1[23]{slash}MCFB1{slash}PWM1[4]{slash}MISO0-Pad37)") (class "Default")
      (node (ref "U2") (pin "37") (pinfunction "P1[23]/MCFB1/PWM1[4]/MISO0_37") (pintype "passive"))
    )
    (net (code "103") (name "unconnected-(U2-P1[24]{slash}MCFB2{slash}PWM1[5]{slash}MOSI0-Pad38)") (class "Default")
      (node (ref "U2") (pin "38") (pinfunction "P1[24]/MCFB2/PWM1[5]/MOSI0_38") (pintype "passive"))
    )
    (net (code "104") (name "unconnected-(U2-P1[25]{slash}MC1A{slash}MAT1[1]-Pad39)") (class "Default")
      (node (ref "U2") (pin "39") (pinfunction "P1[25]/MC1A/MAT1[1]_39") (pintype "passive"))
    )
    (net (code "105") (name "unconnected-(U2-P1[26]{slash}MC1B{slash}PWM1[6]{slash}CAP0[0]-Pad40)") (class "Default")
      (node (ref "U2") (pin "40") (pinfunction "P1[26]/MC1B/PWM1[6]/CAP0[0]_40") (pintype "passive"))
    )
    (net (code "106") (name "unconnected-(U2-P1[27]{slash}CLKOUT{slash}~{USB_OVRCR}{slash}CAP0[1]-Pad43)") (class "Default")
      (node (ref "U2") (pin "43") (pinfunction "P1[27]/CLKOUT/~{USB_OVRCR}/CAP0[1]_43") (pintype "passive"))
    )
    (net (code "107") (name "unconnected-(U2-P1[28]{slash}MC2A{slash}PCAP1[0]{slash}MAT0[0]-Pad44)") (class "Default")
      (node (ref "U2") (pin "44") (pinfunction "P1[28]/MC2A/PCAP1[0]/MAT0[0]_44") (pintype "passive"))
    )
    (net (code "108") (name "unconnected-(U2-P1[29]{slash}MC2B{slash}PCAP1[1]{slash}MAT0[1]-Pad45)") (class "Default")
      (node (ref "U2") (pin "45") (pinfunction "P1[29]/MC2B/PCAP1[1]/MAT0[1]_45") (pintype "passive"))
    )
    (net (code "109") (name "unconnected-(U2-P1[30]{slash}VBUS{slash}AD0[4]-Pad21)") (class "Default")
      (node (ref "U2") (pin "21") (pinfunction "P1[30]/VBUS/AD0[4]_21") (pintype "passive"))
    )
    (net (code "110") (name "unconnected-(U2-P1[31]{slash}SCK1{slash}AD0[5]-Pad20)") (class "Default")
      (node (ref "U2") (pin "20") (pinfunction "P1[31]/SCK1/AD0[5]_20") (pintype "passive"))
    )
    (net (code "111") (name "unconnected-(U2-P2[2]{slash}PWM1[3]{slash}CTS1{slash}TRACEDATA[3]-Pad73)") (class "Default")
      (node (ref "U2") (pin "73") (pinfunction "P2[2]/PWM1[3]/CTS1/TRACEDATA[3]_73") (pintype "passive+no_connect"))
    )
    (net (code "112") (name "unconnected-(U2-P2[3]{slash}PWM1[4]{slash}DCD1{slash}TRACEDATA[2]-Pad70)") (class "Default")
      (node (ref "U2") (pin "70") (pinfunction "P2[3]/PWM1[4]/DCD1/TRACEDATA[2]_70") (pintype "passive+no_connect"))
    )
    (net (code "113") (name "unconnected-(U2-P2[4]{slash}PWM1[5]{slash}DSR1{slash}TRACEDATA[1]-Pad69)") (class "Default")
      (node (ref "U2") (pin "69") (pinfunction "P2[4]/PWM1[5]/DSR1/TRACEDATA[1]_69") (pintype "passive"))
    )
    (net (code "114") (name "unconnected-(U2-P2[8]{slash}TD2{slash}TXD2-Pad65)") (class "Default")
      (node (ref "U2") (pin "65") (pinfunction "P2[8]/TD2/TXD2_65") (pintype "passive+no_connect"))
    )
    (net (code "115") (name "unconnected-(U2-P2[11]{slash}~{EINT1}{slash}I2STX_CLK-Pad52)") (class "Default")
      (node (ref "U2") (pin "52") (pinfunction "P2[11]/~{EINT1}/I2STX_CLK_52") (pintype "passive"))
    )
    (net (code "116") (name "unconnected-(U2-P2[12]{slash}~{EINT2}{slash}I2STX_WS-Pad51)") (class "Default")
      (node (ref "U2") (pin "51") (pinfunction "P2[12]/~{EINT2}/I2STX_WS_51") (pintype "passive"))
    )
    (net (code "117") (name "unconnected-(U2-P4[28]{slash}RX_MCLK{slash}MAT2[0]{slash}TXD3-Pad82)") (class "Default")
      (node (ref "U2") (pin "82") (pinfunction "P4[28]/RX_MCLK/MAT2[0]/TXD3_82") (pintype "passive"))
    )
    (net (code "118") (name "unconnected-(U2-P4[29]{slash}TX_MCLK{slash}MAT2[1]{slash}RXD3-Pad85)") (class "Default")
      (node (ref "U2") (pin "85") (pinfunction "P4[29]/TX_MCLK/MAT2[1]/RXD3_85") (pintype "passive"))
    )
    (net (code "119") (name "unconnected-(U2-RTCK-Pad100)") (class "Default")
      (node (ref "U2") (pin "100") (pinfunction "RTCK_100") (pintype "passive"))
    )
    (net (code "120") (name "unconnected-(U2-TDI-Pad2)") (class "Default")
      (node (ref "U2") (pin "2") (pinfunction "TDI_2") (pintype "passive+no_connect"))
    )
    (net (code "121") (name "unconnected-(U2-TDO{slash}SWO-Pad1)") (class "Default")
      (node (ref "U2") (pin "1") (pinfunction "TDO/SWO_1") (pintype "passive+no_connect"))
    )
    (net (code "122") (name "unconnected-(U2-VBAT-Pad19)") (class "Default")
      (node (ref "U2") (pin "19") (pinfunction "VBAT_19") (pintype "passive"))
    )
    (net (code "123") (name "unconnected-(U2-VREF+-Pad12)") (class "Default")
      (node (ref "U2") (pin "12") (pinfunction "VREF+_12") (pintype "passive"))
    )
    (net (code "124") (name "unconnected-(U2-~{RSTOUT}-Pad14)") (class "Default")
      (node (ref "U2") (pin "14") (pinfunction "~{RSTOUT}_14") (pintype "passive"))
    )
    (net (code "125") (name "unconnected-(U2-~{TRST}-Pad4)") (class "Default")
      (node (ref "U2") (pin "4") (pinfunction "~{TRST}_4") (pintype "passive+no_connect"))
    )
    (net (code "126") (name "unconnected-(USB1-NC-Pad4)") (class "Default")
      (node (ref "USB1") (pin "4") (pinfunction "NC_4") (pintype "passive+no_connect"))
    )
  )
)
